# heatgun.net
KiCad netlist of a schematic drawn in EAGLE
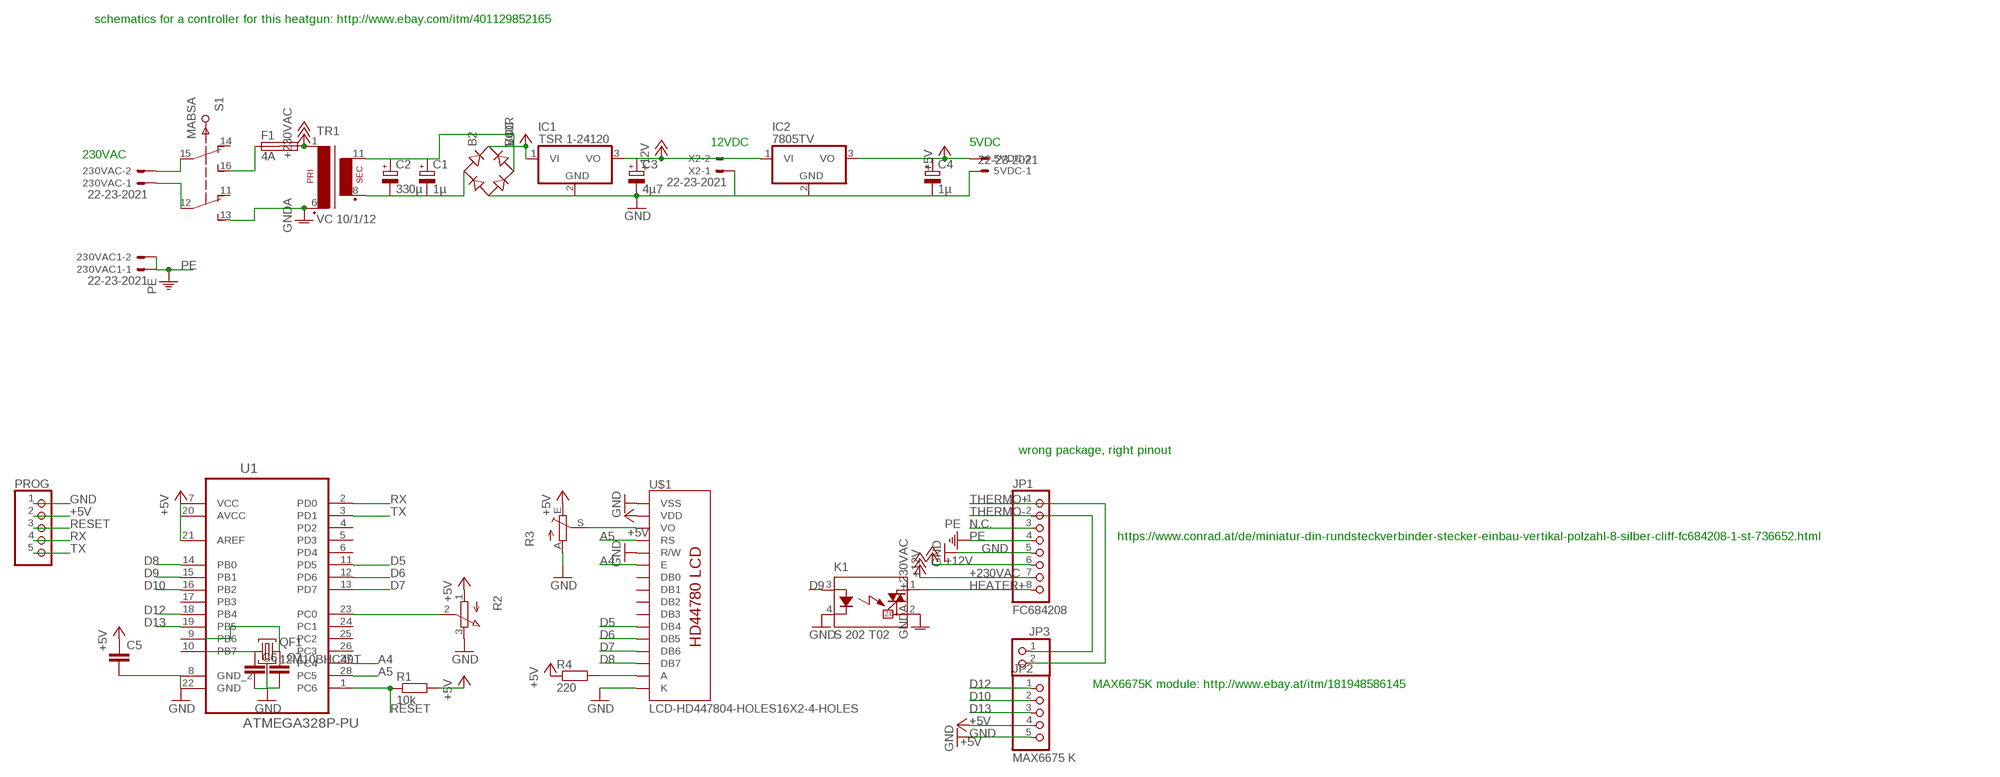
[diagram p0: schematic, sheet 1]

(export (version "E")
  (design (tool "Eeschema 10.0.6"))
  (components
    (comp (ref "5VDC")
      (value "22-23-2021")
      (footprint "eagle-import:22-23-2021")
      (fields (field (name "MF") "MOLEX"))
      (libsource (lib "eagle-import") (part "22-23-2021"))
    )
    (comp (ref "230VAC")
      (value "22-23-2021")
      (footprint "eagle-import:22-23-2021")
      (fields (field (name "MF") "MOLEX"))
      (libsource (lib "eagle-import") (part "22-23-2021"))
    )
    (comp (ref "230VAC1")
      (value "22-23-2021")
      (footprint "eagle-import:22-23-2021")
      (fields (field (name "MF") "MOLEX"))
      (libsource (lib "eagle-import") (part "22-23-2021"))
    )
    (comp (ref "B2")
      (value "B40R")
      (footprint "eagle-import:RB1A")
      (libsource (lib "eagle-import") (part "RECTIFIER-RB1A"))
    )
    (comp (ref "C1")
      (value "1µ")
      (footprint "eagle-import:EB25D")
      (libsource (lib "eagle-import") (part "CPOL-EUE10-25"))
    )
    (comp (ref "C2")
      (value "330µ")
      (footprint "eagle-import:E2-4")
      (libsource (lib "eagle-import") (part "CPOL-EUE2-4"))
    )
    (comp (ref "C3")
      (value "4µ7")
      (footprint "eagle-import:E2-4")
      (libsource (lib "eagle-import") (part "CPOL-EUE2-4"))
    )
    (comp (ref "C4")
      (value "1µ")
      (footprint "eagle-import:E2-4")
      (libsource (lib "eagle-import") (part "CPOL-EUE2-4"))
    )
    (comp (ref "C5")
      (value "C-EU025-025X050")
      (footprint "eagle-import:C025-025X050")
      (libsource (lib "eagle-import") (part "C-EU025-025X050"))
    )
    (comp (ref "C6")
      (value "C-EU025-024X044")
      (footprint "eagle-import:C025-024X044")
      (libsource (lib "eagle-import") (part "C-EU025-024X044"))
    )
    (comp (ref "C7")
      (value "C-EU025-024X044")
      (footprint "eagle-import:C025-024X044")
      (libsource (lib "eagle-import") (part "C-EU025-024X044"))
    )
    (comp (ref "F1")
      (value "4A")
      (footprint "eagle-import:SHK20L")
      (libsource (lib "eagle-import") (part "SHK20L"))
    )
    (comp (ref "IC1")
      (value "TSR 1-24120")
      (footprint "eagle-import:TO220V")
      (libsource (lib "eagle-import") (part "78TV12"))
    )
    (comp (ref "IC2")
      (value "7805TV")
      (footprint "eagle-import:TO220V")
      (libsource (lib "eagle-import") (part "78TV05"))
    )
    (comp (ref "JP1")
      (value "FC684208")
      (footprint "eagle-import:1X08")
      (libsource (lib "eagle-import") (part "PINHD-1X8"))
    )
    (comp (ref "JP2")
      (value "MAX6675 K")
      (footprint "eagle-import:1X05")
      (libsource (lib "eagle-import") (part "PINHD-1X5"))
    )
    (comp (ref "JP3")
      (value "PINHD-1X2")
      (footprint "eagle-import:1X02")
      (libsource (lib "eagle-import") (part "PINHD-1X2"))
    )
    (comp (ref "K1")
      (value "S 202 T02")
      (footprint "eagle-import:S202S02")
      (libsource (lib "eagle-import") (part "S02S021"))
    )
    (comp (ref "PROG")
      (value "PINHD-1X5")
      (footprint "eagle-import:1X05")
      (libsource (lib "eagle-import") (part "PINHD-1X5"))
    )
    (comp (ref "QF1")
      (value "12M10BHC49T")
      (footprint "eagle-import:HC49U")
      (libsource (lib "eagle-import") (part "12M10BHC49T"))
    )
    (comp (ref "R1")
      (value "10k")
      (footprint "eagle-import:0207_2V")
      (libsource (lib "eagle-import") (part "R-EU_0207/2V"))
    )
    (comp (ref "R2")
      (value "3RP/1610N")
      (footprint "eagle-import:3RP_1610N")
      (libsource (lib "eagle-import") (part "3RP/1610N"))
    )
    (comp (ref "R3")
      (value "TRIM_EU-B64Y")
      (footprint "eagle-import:B64Y")
      (libsource (lib "eagle-import") (part "TRIM_EU-B64Y"))
    )
    (comp (ref "R4")
      (value "220")
      (footprint "eagle-import:0207_2V")
      (libsource (lib "eagle-import") (part "R-EU_0207/2V"))
    )
    (comp (ref "S1")
      (value "MABSA")
      (footprint "eagle-import:MABSA")
      (libsource (lib "eagle-import") (part "MABSA"))
    )
    (comp (ref "TR1")
      (value "VC 10/1/12")
      (footprint "eagle-import:EI48-1")
      (libsource (lib "eagle-import") (part "EI48-1"))
    )
    (comp (ref "U$1")
      (value "LCD-HD447804-HOLES16X2-4-HOLES")
      (footprint "eagle-import:LCD-16X2-4HOLES")
      (libsource (lib "eagle-import") (part "LCD-HD4478016X2-4-HOLES4-HOLES"))
    )
    (comp (ref "U1")
      (value "ATMEGA328P-PU")
      (footprint "eagle-import:DIP254P762X457-28")
      (libsource (lib "eagle-import") (part "ATMEGA328P-PU"))
    )
    (comp (ref "X2")
      (value "22-23-2021")
      (footprint "eagle-import:22-23-2021")
      (fields (field (name "MF") "MOLEX"))
      (libsource (lib "eagle-import") (part "22-23-2021"))
    )
  )
  (nets
    (net (code "1") (name "+5V") (class "Default")
      (node (ref "5VDC") (pin "2") (pinfunction "S_2") (pintype "passive"))
      (node (ref "C4") (pin "+") (pinfunction "+_+") (pintype "passive"))
      (node (ref "C5") (pin "1") (pinfunction "1_1") (pintype "passive"))
      (node (ref "IC2") (pin "3") (pinfunction "VO_3") (pintype "passive"))
      (node (ref "JP2") (pin "4") (pinfunction "4_4") (pintype "passive"))
      (node (ref "PROG") (pin "2") (pinfunction "2_2") (pintype "passive"))
      (node (ref "R1") (pin "2") (pinfunction "2_2") (pintype "passive"))
      (node (ref "R2") (pin "1") (pinfunction "A_1") (pintype "passive"))
      (node (ref "R3") (pin "E") (pinfunction "E_E") (pintype "passive"))
      (node (ref "R4") (pin "1") (pinfunction "1_1") (pintype "passive"))
      (node (ref "U$1") (pin "2") (pinfunction "VDD_2") (pintype "power_in"))
      (node (ref "U1") (pin "20") (pinfunction "AVCC_20") (pintype "power_in"))
      (node (ref "U1") (pin "21") (pinfunction "AREF_21") (pintype "input"))
      (node (ref "U1") (pin "7") (pinfunction "VCC_7") (pintype "power_in"))
    )
    (net (code "2") (name "+12V") (class "Default")
      (node (ref "C3") (pin "+") (pinfunction "+_+") (pintype "passive"))
      (node (ref "IC1") (pin "3") (pinfunction "VO_3") (pintype "passive"))
      (node (ref "IC2") (pin "1") (pinfunction "VI_1") (pintype "input"))
      (node (ref "JP1") (pin "6") (pinfunction "6_6") (pintype "passive"))
      (node (ref "X2") (pin "2") (pinfunction "S_2") (pintype "passive"))
    )
    (net (code "3") (name "+230VAC") (class "Default")
      (node (ref "F1") (pin "2A") (pinfunction "2A_2A") (pintype "passive"))
      (node (ref "JP1") (pin "7") (pinfunction "7_7") (pintype "passive"))
      (node (ref "TR1") (pin "1") (pinfunction "P1_1") (pintype "passive"))
    )
    (net (code "4") (name "/A4") (class "Default")
      (node (ref "U$1") (pin "6") (pinfunction "E_6") (pintype "input"))
      (node (ref "U1") (pin "27") (pinfunction "PC4_27") (pintype "bidirectional"))
    )
    (net (code "5") (name "/A5") (class "Default")
      (node (ref "U$1") (pin "4") (pinfunction "RS_4") (pintype "input"))
      (node (ref "U1") (pin "28") (pinfunction "PC5_28") (pintype "bidirectional"))
    )
    (net (code "6") (name "/D5") (class "Default")
      (node (ref "U$1") (pin "11") (pinfunction "DB4_11") (pintype "bidirectional"))
      (node (ref "U1") (pin "11") (pinfunction "PD5_11") (pintype "bidirectional"))
    )
    (net (code "7") (name "/D6") (class "Default")
      (node (ref "U$1") (pin "12") (pinfunction "DB5_12") (pintype "bidirectional"))
      (node (ref "U1") (pin "12") (pinfunction "PD6_12") (pintype "bidirectional"))
    )
    (net (code "8") (name "/D7") (class "Default")
      (node (ref "U$1") (pin "13") (pinfunction "DB6_13") (pintype "bidirectional"))
      (node (ref "U1") (pin "13") (pinfunction "PD7_13") (pintype "bidirectional"))
    )
    (net (code "9") (name "/D8") (class "Default")
      (node (ref "U$1") (pin "14") (pinfunction "DB7_14") (pintype "bidirectional"))
      (node (ref "U1") (pin "14") (pinfunction "PB0_14") (pintype "bidirectional"))
    )
    (net (code "10") (name "/D9") (class "Default")
      (node (ref "K1") (pin "3") (pinfunction "A_3") (pintype "passive"))
      (node (ref "U1") (pin "15") (pinfunction "PB1_15") (pintype "bidirectional"))
    )
    (net (code "11") (name "/D10") (class "Default")
      (node (ref "JP2") (pin "2") (pinfunction "2_2") (pintype "passive"))
      (node (ref "U1") (pin "16") (pinfunction "PB2_16") (pintype "bidirectional"))
    )
    (net (code "12") (name "/D12") (class "Default")
      (node (ref "JP2") (pin "1") (pinfunction "1_1") (pintype "passive"))
      (node (ref "U1") (pin "18") (pinfunction "PB4_18") (pintype "bidirectional"))
    )
    (net (code "13") (name "/D13") (class "Default")
      (node (ref "JP2") (pin "3") (pinfunction "3_3") (pintype "passive"))
      (node (ref "U1") (pin "19") (pinfunction "PB5_19") (pintype "bidirectional"))
    )
    (net (code "14") (name "/HEATER+") (class "Default")
      (node (ref "JP1") (pin "8") (pinfunction "8_8") (pintype "passive"))
      (node (ref "K1") (pin "1") (pinfunction "DS1_1") (pintype "passive"))
    )
    (net (code "15") (name "/N.C.") (class "Default")
      (node (ref "JP1") (pin "3") (pinfunction "3_3") (pintype "passive"))
    )
    (net (code "16") (name "/RESET") (class "Default")
      (node (ref "PROG") (pin "3") (pinfunction "3_3") (pintype "passive"))
      (node (ref "R1") (pin "1") (pinfunction "1_1") (pintype "passive"))
      (node (ref "U1") (pin "1") (pinfunction "PC6_1") (pintype "bidirectional"))
    )
    (net (code "17") (name "/RX") (class "Default")
      (node (ref "PROG") (pin "4") (pinfunction "4_4") (pintype "passive"))
      (node (ref "U1") (pin "2") (pinfunction "PD0_2") (pintype "bidirectional"))
    )
    (net (code "18") (name "/THERMO+") (class "Default")
      (node (ref "JP1") (pin "1") (pinfunction "1_1") (pintype "passive"))
      (node (ref "JP3") (pin "2") (pinfunction "2_2") (pintype "passive"))
    )
    (net (code "19") (name "/THERMO-") (class "Default")
      (node (ref "JP1") (pin "2") (pinfunction "2_2") (pintype "passive"))
      (node (ref "JP3") (pin "1") (pinfunction "1_1") (pintype "passive"))
    )
    (net (code "20") (name "/TX") (class "Default")
      (node (ref "PROG") (pin "5") (pinfunction "5_5") (pintype "passive"))
      (node (ref "U1") (pin "3") (pinfunction "PD1_3") (pintype "bidirectional"))
    )
    (net (code "21") (name "GND") (class "Default")
      (node (ref "5VDC") (pin "1") (pinfunction "S_1") (pintype "passive"))
      (node (ref "B2") (pin "-") (pinfunction "-_-") (pintype "passive"))
      (node (ref "C3") (pin "-") (pinfunction "-_-") (pintype "passive"))
      (node (ref "C4") (pin "-") (pinfunction "-_-") (pintype "passive"))
      (node (ref "C5") (pin "2") (pinfunction "2_2") (pintype "passive"))
      (node (ref "C6") (pin "2") (pinfunction "2_2") (pintype "passive"))
      (node (ref "C7") (pin "2") (pinfunction "2_2") (pintype "passive"))
      (node (ref "IC1") (pin "2") (pinfunction "GND_2") (pintype "passive"))
      (node (ref "IC2") (pin "2") (pinfunction "GND_2") (pintype "passive"))
      (node (ref "JP1") (pin "5") (pinfunction "5_5") (pintype "passive"))
      (node (ref "JP2") (pin "5") (pinfunction "5_5") (pintype "passive"))
      (node (ref "K1") (pin "4") (pinfunction "K_4") (pintype "passive"))
      (node (ref "PROG") (pin "1") (pinfunction "1_1") (pintype "passive"))
      (node (ref "QF1") (pin "2") (pinfunction "2_2") (pintype "passive"))
      (node (ref "R2") (pin "3") (pinfunction "E_3") (pintype "passive"))
      (node (ref "R3") (pin "A") (pinfunction "A_A") (pintype "passive"))
      (node (ref "U$1") (pin "1") (pinfunction "VSS_1") (pintype "power_in"))
      (node (ref "U$1") (pin "16") (pinfunction "K_16") (pintype "power_in"))
      (node (ref "U$1") (pin "5") (pinfunction "R/W_5") (pintype "input"))
      (node (ref "U1") (pin "22") (pinfunction "GND_22") (pintype "passive"))
      (node (ref "U1") (pin "8") (pinfunction "GND_2_8") (pintype "passive"))
      (node (ref "X2") (pin "1") (pinfunction "S_1") (pintype "passive"))
    )
    (net (code "22") (name "GNDA") (class "Default")
      (node (ref "K1") (pin "2") (pinfunction "DS2_2") (pintype "passive"))
      (node (ref "S1") (pin "13") (pinfunction "13_13") (pintype "passive"))
      (node (ref "TR1") (pin "6") (pinfunction "P2_6") (pintype "passive"))
    )
    (net (code "23") (name "Net-(230VACA-S)") (class "Default")
      (node (ref "230VAC") (pin "1") (pinfunction "S_1") (pintype "passive"))
      (node (ref "S1") (pin "12") (pinfunction "12_12") (pintype "passive"))
    )
    (net (code "24") (name "Net-(230VACB-S)") (class "Default")
      (node (ref "230VAC") (pin "2") (pinfunction "S_2") (pintype "passive"))
      (node (ref "S1") (pin "15") (pinfunction "15_15") (pintype "passive"))
    )
    (net (code "25") (name "Net-(C6-Pad1)") (class "Default")
      (node (ref "C6") (pin "1") (pinfunction "1_1") (pintype "passive"))
      (node (ref "QF1") (pin "1") (pinfunction "1_1") (pintype "passive"))
    )
    (net (code "26") (name "Net-(C7-Pad1)") (class "Default")
      (node (ref "C7") (pin "1") (pinfunction "1_1") (pintype "passive"))
      (node (ref "QF1") (pin "3") (pinfunction "3_3") (pintype "passive"))
    )
    (net (code "27") (name "Net-(F1-Pad1A)") (class "Default")
      (node (ref "F1") (pin "1A") (pinfunction "1A_1A") (pintype "passive"))
      (node (ref "S1") (pin "16") (pinfunction "16_16") (pintype "passive"))
    )
    (net (code "28") (name "Net-(R2-S)") (class "Default")
      (node (ref "R2") (pin "2") (pinfunction "S_2") (pintype "passive"))
      (node (ref "U1") (pin "23") (pinfunction "PC0_23") (pintype "bidirectional"))
    )
    (net (code "29") (name "Net-(TR1-S3)") (class "Default")
      (node (ref "B2") (pin "AC1") (pinfunction "AC1_AC1") (pintype "passive"))
      (node (ref "C1") (pin "-") (pinfunction "-_-") (pintype "passive"))
      (node (ref "C2") (pin "-") (pinfunction "-_-") (pintype "passive"))
      (node (ref "TR1") (pin "8") (pinfunction "S3_8") (pintype "passive"))
    )
    (net (code "30") (name "Net-(TR1-S4)") (class "Default")
      (node (ref "B2") (pin "AC2") (pinfunction "AC2_AC2") (pintype "passive"))
      (node (ref "C1") (pin "+") (pinfunction "+_+") (pintype "passive"))
      (node (ref "C2") (pin "+") (pinfunction "+_+") (pintype "passive"))
      (node (ref "TR1") (pin "11") (pinfunction "S4_11") (pintype "passive"))
    )
    (net (code "31") (name "Net-(U$1-A)") (class "Default")
      (node (ref "R4") (pin "2") (pinfunction "2_2") (pintype "passive"))
      (node (ref "U$1") (pin "15") (pinfunction "A_15") (pintype "power_in"))
    )
    (net (code "32") (name "Net-(U$1-VO)") (class "Default")
      (node (ref "R3") (pin "S") (pinfunction "S_S") (pintype "passive"))
      (node (ref "U$1") (pin "3") (pinfunction "VO_3") (pintype "bidirectional"))
    )
    (net (code "33") (name "PE") (class "Default")
      (node (ref "230VAC1") (pin "1") (pinfunction "S_1") (pintype "passive"))
      (node (ref "230VAC1") (pin "2") (pinfunction "S_2") (pintype "passive"))
      (node (ref "JP1") (pin "4") (pinfunction "4_4") (pintype "passive"))
    )
    (net (code "34") (name "VCC") (class "Default")
      (node (ref "B2") (pin "+") (pinfunction "+_+") (pintype "passive"))
      (node (ref "IC1") (pin "1") (pinfunction "VI_1") (pintype "input"))
    )
    (net (code "35") (name "unconnected-(F1-Pad1B)") (class "Default")
      (node (ref "F1") (pin "1B") (pinfunction "1B_1B") (pintype "passive"))
    )
    (net (code "36") (name "unconnected-(F1-Pad2B)") (class "Default")
      (node (ref "F1") (pin "2B") (pinfunction "2B_2B") (pintype "passive"))
    )
    (net (code "37") (name "unconnected-(S1-Pad11)") (class "Default")
      (node (ref "S1") (pin "11") (pinfunction "11_11") (pintype "passive"))
    )
    (net (code "38") (name "unconnected-(S1-Pad14)") (class "Default")
      (node (ref "S1") (pin "14") (pinfunction "14_14") (pintype "passive"))
    )
    (net (code "39") (name "unconnected-(U$1-DB0-Pad7)") (class "Default")
      (node (ref "U$1") (pin "7") (pinfunction "DB0_7") (pintype "bidirectional"))
    )
    (net (code "40") (name "unconnected-(U$1-DB1-Pad8)") (class "Default")
      (node (ref "U$1") (pin "8") (pinfunction "DB1_8") (pintype "bidirectional"))
    )
    (net (code "41") (name "unconnected-(U$1-DB2-Pad9)") (class "Default")
      (node (ref "U$1") (pin "9") (pinfunction "DB2_9") (pintype "bidirectional"))
    )
    (net (code "42") (name "unconnected-(U$1-DB3-Pad10)") (class "Default")
      (node (ref "U$1") (pin "10") (pinfunction "DB3_10") (pintype "bidirectional"))
    )
    (net (code "43") (name "unconnected-(U1-PB3-Pad17)") (class "Default")
      (node (ref "U1") (pin "17") (pinfunction "PB3_17") (pintype "bidirectional"))
    )
    (net (code "44") (name "unconnected-(U1-PB6-Pad9)") (class "Default")
      (node (ref "U1") (pin "9") (pinfunction "PB6_9") (pintype "bidirectional"))
    )
    (net (code "45") (name "unconnected-(U1-PB7-Pad10)") (class "Default")
      (node (ref "U1") (pin "10") (pinfunction "PB7_10") (pintype "bidirectional"))
    )
    (net (code "46") (name "unconnected-(U1-PC1-Pad24)") (class "Default")
      (node (ref "U1") (pin "24") (pinfunction "PC1_24") (pintype "bidirectional"))
    )
    (net (code "47") (name "unconnected-(U1-PC2-Pad25)") (class "Default")
      (node (ref "U1") (pin "25") (pinfunction "PC2_25") (pintype "bidirectional"))
    )
    (net (code "48") (name "unconnected-(U1-PC3-Pad26)") (class "Default")
      (node (ref "U1") (pin "26") (pinfunction "PC3_26") (pintype "bidirectional"))
    )
    (net (code "49") (name "unconnected-(U1-PD2-Pad4)") (class "Default")
      (node (ref "U1") (pin "4") (pinfunction "PD2_4") (pintype "bidirectional"))
    )
    (net (code "50") (name "unconnected-(U1-PD3-Pad5)") (class "Default")
      (node (ref "U1") (pin "5") (pinfunction "PD3_5") (pintype "bidirectional"))
    )
    (net (code "51") (name "unconnected-(U1-PD4-Pad6)") (class "Default")
      (node (ref "U1") (pin "6") (pinfunction "PD4_6") (pintype "bidirectional"))
    )
  )
)
